# Sheet2.net
KiCad netlist of a schematic drawn in Altium Designer
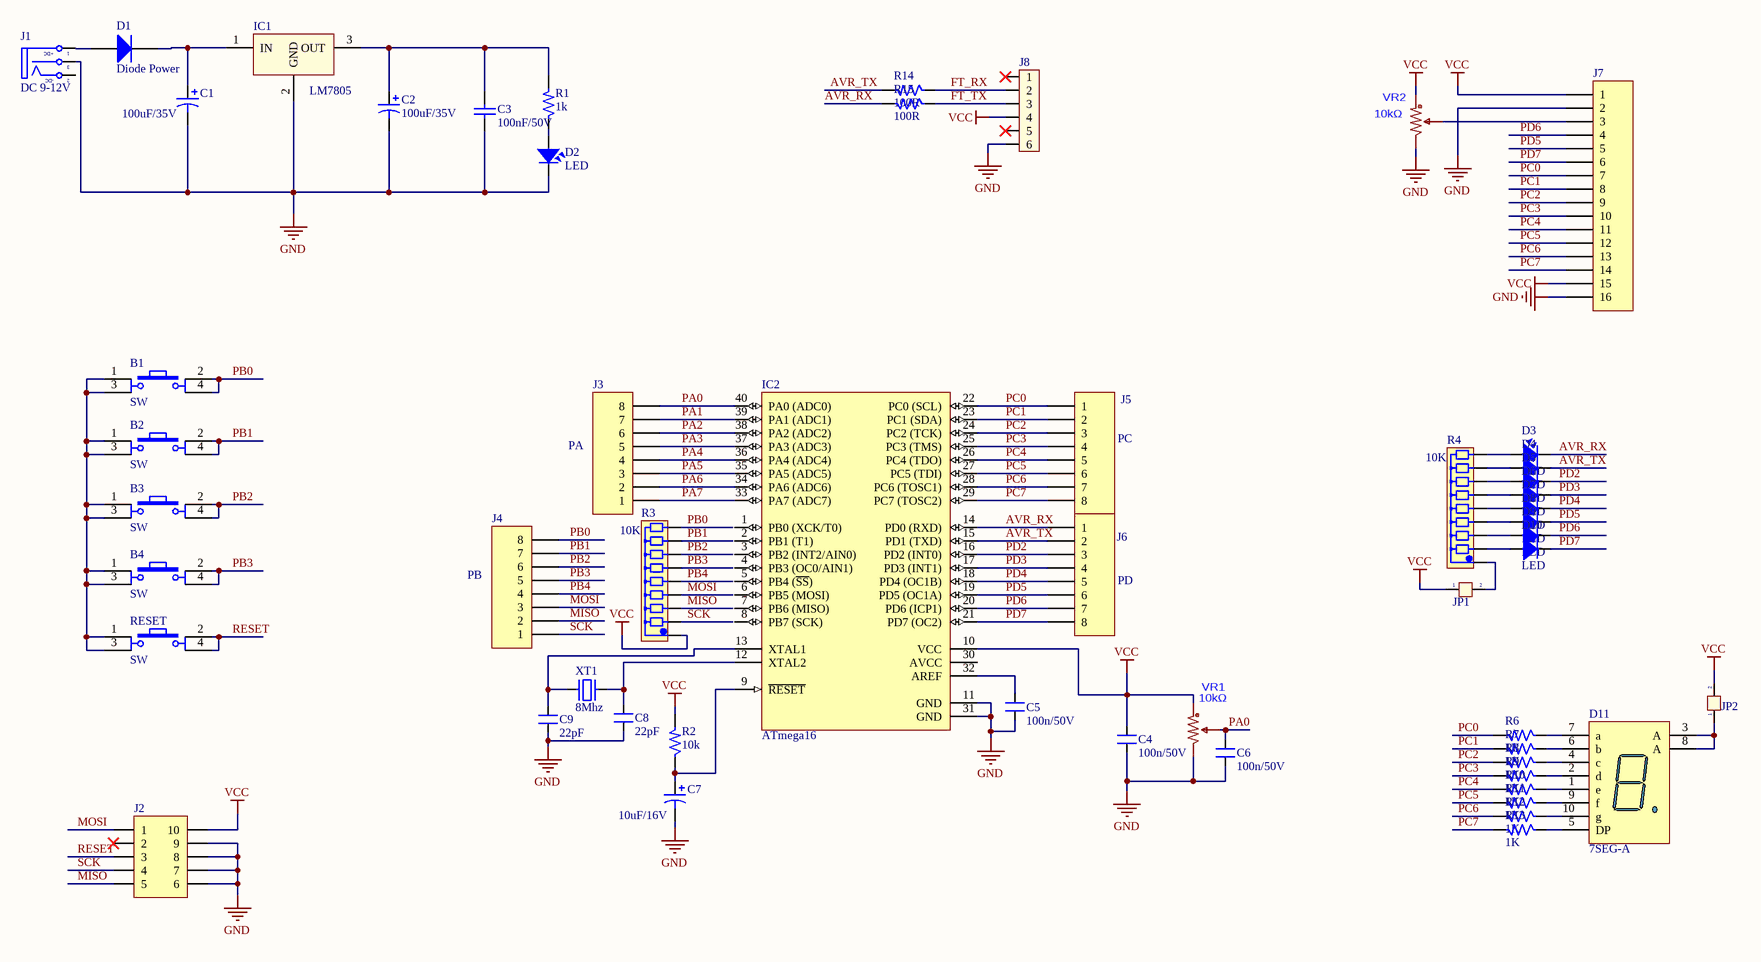
[diagram p0: Sheet2.SchDoc]

(export (version "E")
  (design (tool "Eeschema 10.0.6"))
  (components
    (comp (ref "B1")
      (value "SW")
      (footprint "SW4")
      (description "Switch button 4 pin")
      (libsource (lib "My Library") (part "SW4"))
    )
    (comp (ref "B2")
      (value "SW")
      (footprint "SW4")
      (description "Switch button 4 pin")
      (libsource (lib "My Library") (part "SW4"))
    )
    (comp (ref "B3")
      (value "SW")
      (footprint "SW4")
      (description "Switch button 4 pin")
      (libsource (lib "My Library") (part "SW4"))
    )
    (comp (ref "B4")
      (value "SW")
      (footprint "SW4")
      (description "Switch button 4 pin")
      (libsource (lib "My Library") (part "SW4"))
    )
    (comp (ref "C1")
      (value "100uF/35V")
      (footprint "C10mm")
      (description "Polarized Capacitor (Axial)")
      (fields (field (name "PUBLISHER") "Altium Limited"))
      (libsource (lib "My Library") (part "Cap Pol 8mm"))
    )
    (comp (ref "C2")
      (value "100uF/35V")
      (footprint "C10mm")
      (description "Polarized Capacitor (Axial)")
      (fields (field (name "PUBLISHER") "Altium Limited"))
      (libsource (lib "My Library") (part "Cap Pol 8mm"))
    )
    (comp (ref "C3")
      (value "100nF/50V")
      (footprint "Tu-pico")
      (description "Capacitor")
      (fields (field (name "Comment") "Capacitor Ceramic") (field (name "PUBLISHER") "Altium Limited"))
      (libsource (lib "My Library") (part "CapCeramic"))
    )
    (comp (ref "C4")
      (value "100n/50V")
      (footprint "CN1")
      (description "Cap np  1pF - 472pF")
      (libsource (lib "My Library") (part "CN1"))
    )
    (comp (ref "C5")
      (value "100n/50V")
      (footprint "CN1")
      (description "Cap np  1pF - 472pF")
      (libsource (lib "My Library") (part "CN1"))
    )
    (comp (ref "C6")
      (value "100n/50V")
      (footprint "CN1")
      (description "Cap np  1pF - 472pF")
      (libsource (lib "My Library") (part "CN1"))
    )
    (comp (ref "C7")
      (value "10uF/16V")
      (footprint "C5mm")
      (description "Polarized Capacitor (Axial)")
      (fields (field (name "PUBLISHER") "Altium Limited"))
      (libsource (lib "My Library") (part "Cap Pol 5mm"))
    )
    (comp (ref "C8")
      (value "22pF")
      (footprint "CN1")
      (description "Cap np  1pF - 472pF")
      (libsource (lib "My Library") (part "CN1"))
    )
    (comp (ref "C9")
      (value "22pF")
      (footprint "CN1")
      (description "Cap np  1pF - 472pF")
      (libsource (lib "My Library") (part "CN1"))
    )
    (comp (ref "D1")
      (value "Diode Power")
      (footprint "DIODE/POW/1A")
      (fields (field (name "PUBLISHER") "Altium Limited"))
      (libsource (lib "My Library") (part "Diode Power"))
    )
    (comp (ref "D2")
      (value "LED")
      (footprint "LED-5TRED")
      (description "LED Single colour Green and Red")
      (libsource (lib "My Library") (part "LED"))
    )
    (comp (ref "D3")
      (value "LED")
      (footprint "LED-5TRED")
      (description "LED Single colour Green and Red")
      (libsource (lib "My Library") (part "LED"))
    )
    (comp (ref "D4")
      (value "LED")
      (footprint "LED-5TRED")
      (description "LED Single colour Green and Red")
      (libsource (lib "My Library") (part "LED"))
    )
    (comp (ref "D5")
      (value "LED")
      (footprint "LED-5TRED")
      (description "LED Single colour Green and Red")
      (libsource (lib "My Library") (part "LED"))
    )
    (comp (ref "D6")
      (value "LED")
      (footprint "LED-5TRED")
      (description "LED Single colour Green and Red")
      (libsource (lib "My Library") (part "LED"))
    )
    (comp (ref "D7")
      (value "LED")
      (footprint "LED-5TRED")
      (description "LED Single colour Green and Red")
      (libsource (lib "My Library") (part "LED"))
    )
    (comp (ref "D8")
      (value "LED")
      (footprint "LED-5TRED")
      (description "LED Single colour Green and Red")
      (libsource (lib "My Library") (part "LED"))
    )
    (comp (ref "D9")
      (value "LED")
      (footprint "LED-5TRED")
      (description "LED Single colour Green and Red")
      (libsource (lib "My Library") (part "LED"))
    )
    (comp (ref "D10")
      (value "LED")
      (footprint "LED-5TRED")
      (description "LED Single colour Green and Red")
      (libsource (lib "My Library") (part "LED"))
    )
    (comp (ref "D11")
      (value "7SEG-A")
      (footprint "LED7SEG")
      (description "14.2 mm General Purpose Blue 7-Segment Display: CA, RH DP, Gray Surface")
      (fields (field (name "PUBLISHER") "Altium Limited"))
      (libsource (lib "My Library") (part "LED7SEG-A"))
    )
    (comp (ref "IC1")
      (value "LM7805")
      (footprint "QTO-220")
      (description "On ap +, from + 5 to + 24VDC")
      (libsource (lib "My Library") (part "LM78xx"))
    )
    (comp (ref "IC2")
      (value "ATmega16")
      (footprint "DIP40/W0.6")
      (description "8-Bit AVR Microcontroller with 16K Bytes of In-System Programmable Flash Memory")
      (libsource (lib "My Library") (part "ATmega16A-PU"))
    )
    (comp (ref "J1")
      (value "DC 9-12V")
      (footprint "DC-IN")
      (description "Jac DC input")
      (libsource (lib "My Library") (part "DCIN"))
    )
    (comp (ref "J2")
      (value "JP5x2")
      (footprint "JP5-D2T")
      (description "WR-PHD 2.54 mm Dual Socket Header")
      (fields
        (field (name "MANUFACTURER") "Würth Elektronik eiSos GmbH")
        (field (name "PARTNO") "61301021821")
        (field (name "CREATED BY") "Karrer Zheng")
      )
      (libsource (lib "My Library") (part "JP5x2"))
    )
    (comp (ref "J3")
      (value "PA")
      (footprint "HDR1X8")
      (description "Header, 8-Pin")
      (fields (field (name "PUBLISHER") "Altium Limited"))
      (libsource (lib "") (part "Header 8_1"))
    )
    (comp (ref "J4")
      (value "PB")
      (footprint "HDR1X8")
      (description "Header, 8-Pin")
      (fields (field (name "PUBLISHER") "Altium Limited"))
      (libsource (lib "") (part "Header 8_1"))
    )
    (comp (ref "J5")
      (value "PC")
      (footprint "HDR1X8")
      (description "Header, 8-Pin")
      (fields (field (name "PUBLISHER") "Altium Limited"))
      (libsource (lib "My Library") (part "Header 8"))
    )
    (comp (ref "J6")
      (value "PD")
      (footprint "HDR1X8")
      (description "Header, 8-Pin")
      (fields (field (name "PUBLISHER") "Altium Limited"))
      (libsource (lib "My Library") (part "Header 8"))
    )
    (comp (ref "J7")
      (value "JP16")
      (footprint "JP16-D1T")
      (description "WR-PHD 2.54 mm Angled Socket Header")
      (fields
        (field (name "MANUFACTURER") "Würth Elektronik eiSos GmbH")
        (field (name "PARTNO") "613016143121")
        (field (name "CREATED BY") "Karrer Zheng")
      )
      (libsource (lib "My Library") (part "JP16"))
    )
    (comp (ref "J8") (value "JP6 PIN") (footprint "JP6") (libsource (lib "My Library") (part "JP6")))
    (comp (ref "JP1") (value "Jumper 2") (footprint "JP2") (libsource (lib "") (part "JP 2_1")))
    (comp (ref "JP2") (value "Jumper 2") (footprint "JP2") (libsource (lib "My Library") (part "JP 2")))
    (comp (ref "R1")
      (value "1k")
      (footprint "R1/4W")
      (description "Resistor 1/4W")
      (libsource (lib "My Library") (part "R"))
    )
    (comp (ref "R2")
      (value "10k")
      (footprint "R1/4W")
      (description "Resistor 1/4W")
      (libsource (lib "My Library") (part "R"))
    )
    (comp (ref "R3")
      (value "10K")
      (footprint "RN8")
      (description "Resistor 8 (Thanh)")
      (libsource (lib "My Library") (part "RN8"))
    )
    (comp (ref "R4")
      (value "10K")
      (footprint "RN8")
      (description "Resistor 8 (Thanh)")
      (libsource (lib "My Library") (part "RN8"))
    )
    (comp (ref "R6")
      (value "1K")
      (footprint "R1/4W")
      (description "Resistor 1/4W")
      (libsource (lib "My Library") (part "R"))
    )
    (comp (ref "R7")
      (value "1K")
      (footprint "R1/4W")
      (description "Resistor 1/4W")
      (libsource (lib "My Library") (part "R"))
    )
    (comp (ref "R8")
      (value "1K")
      (footprint "R1/4W")
      (description "Resistor 1/4W")
      (libsource (lib "My Library") (part "R"))
    )
    (comp (ref "R9")
      (value "1K")
      (footprint "R1/4W")
      (description "Resistor 1/4W")
      (libsource (lib "My Library") (part "R"))
    )
    (comp (ref "R10")
      (value "1K")
      (footprint "R1/4W")
      (description "Resistor 1/4W")
      (libsource (lib "My Library") (part "R"))
    )
    (comp (ref "R11")
      (value "1K")
      (footprint "R1/4W")
      (description "Resistor 1/4W")
      (libsource (lib "My Library") (part "R"))
    )
    (comp (ref "R12")
      (value "1K")
      (footprint "R1/4W")
      (description "Resistor 1/4W")
      (libsource (lib "My Library") (part "R"))
    )
    (comp (ref "R13")
      (value "1K")
      (footprint "R1/4W")
      (description "Resistor 1/4W")
      (libsource (lib "My Library") (part "R"))
    )
    (comp (ref "R14")
      (value "100R")
      (footprint "R1/4W")
      (description "Resistor 1/4W")
      (libsource (lib "My Library") (part "R"))
    )
    (comp (ref "R15")
      (value "100R")
      (footprint "R1/4W")
      (description "Resistor 1/4W")
      (libsource (lib "My Library") (part "R"))
    )
    (comp (ref "RESET")
      (value "SW")
      (footprint "SW4")
      (description "Switch button 4 pin")
      (libsource (lib "My Library") (part "SW4"))
    )
    (comp (ref "VR1")
      (value "10kΩ")
      (footprint "RES-ADJ-SMD_RM065-V1")
      (description "VR-10K")
      (libsource (lib "My_Library_DPD_V2") (part "VR-RM065-103(10K)"))
    )
    (comp (ref "VR2")
      (value "10kΩ")
      (footprint "RES-ADJ-SMD_RM065-V1")
      (description "VR-10K")
      (libsource (lib "My_Library_DPD_V2") (part "VR-RM065-103(10K)"))
    )
    (comp (ref "XT1")
      (value "8Mhz")
      (footprint "XT2")
      (description "Crystal For all Crystal 2pin.")
      (libsource (lib "My Library") (part "XT2"))
    )
  )
  (nets
    (net (code "1") (name "/AVR_RX") (class "Default")
      (node (ref "D3") (pin "2") (pinfunction "2_2") (pintype "passive"))
      (node (ref "IC2") (pin "14") (pinfunction "PD0_(RXD)_14") (pintype "bidirectional"))
      (node (ref "J6") (pin "1") (pinfunction "1_1") (pintype "passive"))
      (node (ref "R15") (pin "2") (pinfunction "2_2") (pintype "passive"))
    )
    (net (code "2") (name "/AVR_TX") (class "Default")
      (node (ref "D4") (pin "2") (pinfunction "2_2") (pintype "passive"))
      (node (ref "IC2") (pin "15") (pinfunction "PD1_(TXD)_15") (pintype "bidirectional"))
      (node (ref "J6") (pin "2") (pinfunction "2_2") (pintype "passive"))
      (node (ref "R14") (pin "2") (pinfunction "2_2") (pintype "passive"))
    )
    (net (code "3") (name "/FT_RX") (class "Default")
      (node (ref "J8") (pin "2") (pinfunction "2_2") (pintype "passive"))
      (node (ref "R14") (pin "1") (pinfunction "1_1") (pintype "passive"))
    )
    (net (code "4") (name "/FT_TX") (class "Default")
      (node (ref "J8") (pin "3") (pinfunction "3_3") (pintype "passive"))
      (node (ref "R15") (pin "1") (pinfunction "1_1") (pintype "passive"))
    )
    (net (code "5") (name "/MISO") (class "Default")
      (node (ref "J2") (pin "5") (pinfunction "5_5") (pintype "passive"))
      (node (ref "J4") (pin "2") (pinfunction "2_2") (pintype "passive"))
      (node (ref "R3") (pin "3") (pinfunction "3_3") (pintype "passive"))
    )
    (net (code "6") (name "/MOSI") (class "Default")
      (node (ref "J2") (pin "1") (pinfunction "1_1") (pintype "passive"))
      (node (ref "J4") (pin "3") (pinfunction "3_3") (pintype "passive"))
      (node (ref "R3") (pin "4") (pinfunction "4_4") (pintype "passive"))
    )
    (net (code "7") (name "/PA0") (class "Default")
      (node (ref "C6") (pin "1") (pinfunction "1_1") (pintype "passive"))
      (node (ref "IC2") (pin "40") (pinfunction "PA0_(ADC0)_40") (pintype "bidirectional"))
      (node (ref "J3") (pin "8") (pinfunction "8_8") (pintype "passive"))
      (node (ref "VR1") (pin "2") (pinfunction "2_2") (pintype "passive"))
    )
    (net (code "8") (name "/PA1") (class "Default")
      (node (ref "IC2") (pin "39") (pinfunction "PA1_(ADC1)_39") (pintype "bidirectional"))
      (node (ref "J3") (pin "7") (pinfunction "7_7") (pintype "passive"))
    )
    (net (code "9") (name "/PA2") (class "Default")
      (node (ref "IC2") (pin "38") (pinfunction "PA2_(ADC2)_38") (pintype "bidirectional"))
      (node (ref "J3") (pin "6") (pinfunction "6_6") (pintype "passive"))
    )
    (net (code "10") (name "/PA3") (class "Default")
      (node (ref "IC2") (pin "37") (pinfunction "PA3_(ADC3)_37") (pintype "bidirectional"))
      (node (ref "J3") (pin "5") (pinfunction "5_5") (pintype "passive"))
    )
    (net (code "11") (name "/PA4") (class "Default")
      (node (ref "IC2") (pin "36") (pinfunction "PA4_(ADC4)_36") (pintype "bidirectional"))
      (node (ref "J3") (pin "4") (pinfunction "4_4") (pintype "passive"))
    )
    (net (code "12") (name "/PA5") (class "Default")
      (node (ref "IC2") (pin "35") (pinfunction "PA5_(ADC5)_35") (pintype "bidirectional"))
      (node (ref "J3") (pin "3") (pinfunction "3_3") (pintype "passive"))
    )
    (net (code "13") (name "/PA6") (class "Default")
      (node (ref "IC2") (pin "34") (pinfunction "PA6_(ADC6)_34") (pintype "bidirectional"))
      (node (ref "J3") (pin "2") (pinfunction "2_2") (pintype "passive"))
    )
    (net (code "14") (name "/PA7") (class "Default")
      (node (ref "IC2") (pin "33") (pinfunction "PA7_(ADC7)_33") (pintype "bidirectional"))
      (node (ref "J3") (pin "1") (pinfunction "1_1") (pintype "passive"))
    )
    (net (code "15") (name "/PB0") (class "Default")
      (node (ref "B1") (pin "2") (pintype "passive"))
      (node (ref "B1") (pin "4") (pintype "passive"))
      (node (ref "J4") (pin "8") (pinfunction "8_8") (pintype "passive"))
      (node (ref "R3") (pin "9") (pinfunction "9_9") (pintype "passive"))
    )
    (net (code "16") (name "/PB1") (class "Default")
      (node (ref "B2") (pin "2") (pintype "passive"))
      (node (ref "B2") (pin "4") (pintype "passive"))
      (node (ref "J4") (pin "7") (pinfunction "7_7") (pintype "passive"))
      (node (ref "R3") (pin "8") (pinfunction "8_8") (pintype "passive"))
    )
    (net (code "17") (name "/PB2") (class "Default")
      (node (ref "B3") (pin "2") (pintype "passive"))
      (node (ref "B3") (pin "4") (pintype "passive"))
      (node (ref "J4") (pin "6") (pinfunction "6_6") (pintype "passive"))
      (node (ref "R3") (pin "7") (pinfunction "7_7") (pintype "passive"))
    )
    (net (code "18") (name "/PB3") (class "Default")
      (node (ref "B4") (pin "2") (pintype "passive"))
      (node (ref "B4") (pin "4") (pintype "passive"))
      (node (ref "J4") (pin "5") (pinfunction "5_5") (pintype "passive"))
      (node (ref "R3") (pin "6") (pinfunction "6_6") (pintype "passive"))
    )
    (net (code "19") (name "/PB4") (class "Default")
      (node (ref "J4") (pin "4") (pinfunction "4_4") (pintype "passive"))
      (node (ref "R3") (pin "5") (pinfunction "5_5") (pintype "passive"))
    )
    (net (code "20") (name "/PC0") (class "Default")
      (node (ref "IC2") (pin "22") (pinfunction "PC0_(SCL)_22") (pintype "bidirectional"))
      (node (ref "J5") (pin "1") (pinfunction "1_1") (pintype "passive"))
      (node (ref "J7") (pin "7") (pinfunction "7_7") (pintype "passive"))
      (node (ref "R6") (pin "2") (pinfunction "2_2") (pintype "passive"))
    )
    (net (code "21") (name "/PC1") (class "Default")
      (node (ref "IC2") (pin "23") (pinfunction "PC1_(SDA)_23") (pintype "bidirectional"))
      (node (ref "J5") (pin "2") (pinfunction "2_2") (pintype "passive"))
      (node (ref "J7") (pin "8") (pinfunction "8_8") (pintype "passive"))
      (node (ref "R7") (pin "2") (pinfunction "2_2") (pintype "passive"))
    )
    (net (code "22") (name "/PC2") (class "Default")
      (node (ref "IC2") (pin "24") (pinfunction "PC2_(TCK)_24") (pintype "bidirectional"))
      (node (ref "J5") (pin "3") (pinfunction "3_3") (pintype "passive"))
      (node (ref "J7") (pin "9") (pinfunction "9_9") (pintype "passive"))
      (node (ref "R8") (pin "2") (pinfunction "2_2") (pintype "passive"))
    )
    (net (code "23") (name "/PC3") (class "Default")
      (node (ref "IC2") (pin "25") (pinfunction "PC3_(TMS)_25") (pintype "bidirectional"))
      (node (ref "J5") (pin "4") (pinfunction "4_4") (pintype "passive"))
      (node (ref "J7") (pin "10") (pinfunction "10_10") (pintype "passive"))
      (node (ref "R9") (pin "2") (pinfunction "2_2") (pintype "passive"))
    )
    (net (code "24") (name "/PC4") (class "Default")
      (node (ref "IC2") (pin "26") (pinfunction "PC4_(TDO)_26") (pintype "bidirectional"))
      (node (ref "J5") (pin "5") (pinfunction "5_5") (pintype "passive"))
      (node (ref "J7") (pin "11") (pinfunction "11_11") (pintype "passive"))
      (node (ref "R10") (pin "2") (pinfunction "2_2") (pintype "passive"))
    )
    (net (code "25") (name "/PC5") (class "Default")
      (node (ref "IC2") (pin "27") (pinfunction "PC5_(TDI)_27") (pintype "bidirectional"))
      (node (ref "J5") (pin "6") (pinfunction "6_6") (pintype "passive"))
      (node (ref "J7") (pin "12") (pinfunction "12_12") (pintype "passive"))
      (node (ref "R11") (pin "2") (pinfunction "2_2") (pintype "passive"))
    )
    (net (code "26") (name "/PC6") (class "Default")
      (node (ref "IC2") (pin "28") (pinfunction "PC6_(TOSC1)_28") (pintype "bidirectional"))
      (node (ref "J5") (pin "7") (pinfunction "7_7") (pintype "passive"))
      (node (ref "J7") (pin "13") (pinfunction "13_13") (pintype "passive"))
      (node (ref "R12") (pin "2") (pinfunction "2_2") (pintype "passive"))
    )
    (net (code "27") (name "/PC7") (class "Default")
      (node (ref "IC2") (pin "29") (pinfunction "PC7_(TOSC2)_29") (pintype "bidirectional"))
      (node (ref "J5") (pin "8") (pinfunction "8_8") (pintype "passive"))
      (node (ref "J7") (pin "14") (pinfunction "14_14") (pintype "passive"))
      (node (ref "R13") (pin "2") (pinfunction "2_2") (pintype "passive"))
    )
    (net (code "28") (name "/PD2") (class "Default")
      (node (ref "D5") (pin "2") (pinfunction "2_2") (pintype "passive"))
      (node (ref "IC2") (pin "16") (pinfunction "PD2_(INT0)_16") (pintype "bidirectional"))
      (node (ref "J6") (pin "3") (pinfunction "3_3") (pintype "passive"))
    )
    (net (code "29") (name "/PD3") (class "Default")
      (node (ref "D6") (pin "2") (pinfunction "2_2") (pintype "passive"))
      (node (ref "IC2") (pin "17") (pinfunction "PD3_(INT1)_17") (pintype "bidirectional"))
      (node (ref "J6") (pin "4") (pinfunction "4_4") (pintype "passive"))
    )
    (net (code "30") (name "/PD4") (class "Default")
      (node (ref "D7") (pin "2") (pinfunction "2_2") (pintype "passive"))
      (node (ref "IC2") (pin "18") (pinfunction "PD4_(OC1B)_18") (pintype "bidirectional"))
      (node (ref "J6") (pin "5") (pinfunction "5_5") (pintype "passive"))
    )
    (net (code "31") (name "/PD5") (class "Default")
      (node (ref "D8") (pin "2") (pinfunction "2_2") (pintype "passive"))
      (node (ref "IC2") (pin "19") (pinfunction "PD5_(OC1A)_19") (pintype "bidirectional"))
      (node (ref "J6") (pin "6") (pinfunction "6_6") (pintype "passive"))
      (node (ref "J7") (pin "5") (pinfunction "5_5") (pintype "passive"))
    )
    (net (code "32") (name "/PD6") (class "Default")
      (node (ref "D9") (pin "2") (pinfunction "2_2") (pintype "passive"))
      (node (ref "IC2") (pin "20") (pinfunction "PD6_(ICP1)_20") (pintype "bidirectional"))
      (node (ref "J6") (pin "7") (pinfunction "7_7") (pintype "passive"))
      (node (ref "J7") (pin "4") (pinfunction "4_4") (pintype "passive"))
    )
    (net (code "33") (name "/PD7") (class "Default")
      (node (ref "D10") (pin "2") (pinfunction "2_2") (pintype "passive"))
      (node (ref "IC2") (pin "21") (pinfunction "PD7_(OC2)_21") (pintype "bidirectional"))
      (node (ref "J6") (pin "8") (pinfunction "8_8") (pintype "passive"))
      (node (ref "J7") (pin "6") (pinfunction "6_6") (pintype "passive"))
    )
    (net (code "34") (name "/RESET") (class "Default")
      (node (ref "J2") (pin "3") (pinfunction "3_3") (pintype "passive"))
      (node (ref "RESET") (pin "2") (pintype "passive"))
      (node (ref "RESET") (pin "4") (pintype "passive"))
    )
    (net (code "35") (name "/SCK") (class "Default")
      (node (ref "J2") (pin "4") (pinfunction "4_4") (pintype "passive"))
      (node (ref "J4") (pin "1") (pinfunction "1_1") (pintype "passive"))
      (node (ref "R3") (pin "2") (pinfunction "2_2") (pintype "passive"))
    )
    (net (code "36") (name "GND") (class "Default")
      (node (ref "C1") (pin "2") (pinfunction "2_2") (pintype "passive"))
      (node (ref "C2") (pin "2") (pinfunction "2_2") (pintype "passive"))
      (node (ref "C3") (pin "1") (pinfunction "1_1") (pintype "passive"))
      (node (ref "C4") (pin "2") (pinfunction "2_2") (pintype "passive"))
      (node (ref "C5") (pin "2") (pinfunction "2_2") (pintype "passive"))
      (node (ref "C6") (pin "2") (pinfunction "2_2") (pintype "passive"))
      (node (ref "C7") (pin "2") (pinfunction "2_2") (pintype "passive"))
      (node (ref "C8") (pin "1") (pinfunction "1_1") (pintype "passive"))
      (node (ref "C9") (pin "1") (pinfunction "1_1") (pintype "passive"))
      (node (ref "D2") (pin "2") (pinfunction "2_2") (pintype "passive"))
      (node (ref "IC1") (pin "2") (pinfunction "GND_2") (pintype "passive"))
      (node (ref "IC2") (pin "11") (pinfunction "GND_11") (pintype "power_in"))
      (node (ref "IC2") (pin "31") (pinfunction "GND_31") (pintype "power_in"))
      (node (ref "J1") (pin "3") (pinfunction "S_3") (pintype "power_in"))
      (node (ref "J2") (pin "6") (pinfunction "6_6") (pintype "passive"))
      (node (ref "J2") (pin "7") (pinfunction "7_7") (pintype "passive"))
      (node (ref "J2") (pin "8") (pinfunction "8_8") (pintype "passive"))
      (node (ref "J2") (pin "9") (pinfunction "9_9") (pintype "passive"))
      (node (ref "J7") (pin "16") (pinfunction "16_16") (pintype "passive"))
      (node (ref "J7") (pin "2") (pinfunction "2_2") (pintype "passive"))
      (node (ref "J8") (pin "6") (pinfunction "6_6") (pintype "passive"))
      (node (ref "VR1") (pin "3") (pinfunction "3_3") (pintype "passive"))
      (node (ref "VR2") (pin "3") (pinfunction "3_3") (pintype "passive"))
    )
    (net (code "37") (name "Net-(B1-Pad1)") (class "Default")
      (node (ref "B1") (pin "1") (pintype "passive"))
      (node (ref "B1") (pin "3") (pintype "passive"))
      (node (ref "B2") (pin "1") (pintype "passive"))
      (node (ref "B2") (pin "3") (pintype "passive"))
      (node (ref "B3") (pin "1") (pintype "passive"))
      (node (ref "B3") (pin "3") (pintype "passive"))
      (node (ref "B4") (pin "1") (pintype "passive"))
      (node (ref "B4") (pin "3") (pintype "passive"))
      (node (ref "RESET") (pin "1") (pintype "passive"))
      (node (ref "RESET") (pin "3") (pintype "passive"))
    )
    (net (code "38") (name "Net-(D1-A)") (class "Default")
      (node (ref "D1") (pin "1") (pinfunction "A_1") (pintype "passive"))
      (node (ref "J1") (pin "1") (pinfunction "T_1") (pintype "passive"))
    )
    (net (code "39") (name "Net-(D1-K)") (class "Default")
      (node (ref "C1") (pin "1") (pinfunction "1_1") (pintype "passive"))
      (node (ref "D1") (pin "2") (pinfunction "K_2") (pintype "passive"))
      (node (ref "IC1") (pin "1") (pinfunction "IN_1") (pintype "passive"))
    )
    (net (code "40") (name "Net-(D2-Pad1)") (class "Default")
      (node (ref "D2") (pin "1") (pinfunction "1_1") (pintype "passive"))
      (node (ref "R1") (pin "1") (pinfunction "1_1") (pintype "passive"))
    )
    (net (code "41") (name "Net-(D3-Pad1)") (class "Default")
      (node (ref "D3") (pin "1") (pinfunction "1_1") (pintype "passive"))
      (node (ref "R4") (pin "9") (pinfunction "9_9") (pintype "passive"))
    )
    (net (code "42") (name "Net-(D4-Pad1)") (class "Default")
      (node (ref "D4") (pin "1") (pinfunction "1_1") (pintype "passive"))
      (node (ref "R4") (pin "8") (pinfunction "8_8") (pintype "passive"))
    )
    (net (code "43") (name "Net-(D5-Pad1)") (class "Default")
      (node (ref "D5") (pin "1") (pinfunction "1_1") (pintype "passive"))
      (node (ref "R4") (pin "7") (pinfunction "7_7") (pintype "passive"))
    )
    (net (code "44") (name "Net-(D6-Pad1)") (class "Default")
      (node (ref "D6") (pin "1") (pinfunction "1_1") (pintype "passive"))
      (node (ref "R4") (pin "6") (pinfunction "6_6") (pintype "passive"))
    )
    (net (code "45") (name "Net-(D7-Pad1)") (class "Default")
      (node (ref "D7") (pin "1") (pinfunction "1_1") (pintype "passive"))
      (node (ref "R4") (pin "5") (pinfunction "5_5") (pintype "passive"))
    )
    (net (code "46") (name "Net-(D8-Pad1)") (class "Default")
      (node (ref "D8") (pin "1") (pinfunction "1_1") (pintype "passive"))
      (node (ref "R4") (pin "4") (pinfunction "4_4") (pintype "passive"))
    )
    (net (code "47") (name "Net-(D9-Pad1)") (class "Default")
      (node (ref "D9") (pin "1") (pinfunction "1_1") (pintype "passive"))
      (node (ref "R4") (pin "3") (pinfunction "3_3") (pintype "passive"))
    )
    (net (code "48") (name "Net-(D10-Pad1)") (class "Default")
      (node (ref "D10") (pin "1") (pinfunction "1_1") (pintype "passive"))
      (node (ref "R4") (pin "2") (pinfunction "2_2") (pintype "passive"))
    )
    (net (code "49") (name "Net-(D11-A-Pad3)") (class "Default")
      (node (ref "D11") (pin "3") (pinfunction "A_3") (pintype "passive"))
      (node (ref "D11") (pin "8") (pinfunction "A_8") (pintype "passive"))
      (node (ref "JP2") (pin "1") (pinfunction "1_1") (pintype "passive"))
    )
    (net (code "50") (name "Net-(D11-DP)") (class "Default")
      (node (ref "D11") (pin "5") (pinfunction "DP_5") (pintype "passive"))
      (node (ref "R13") (pin "1") (pinfunction "1_1") (pintype "passive"))
    )
    (net (code "51") (name "Net-(D11-a)") (class "Default")
      (node (ref "D11") (pin "7") (pinfunction "a_7") (pintype "passive"))
      (node (ref "R6") (pin "1") (pinfunction "1_1") (pintype "passive"))
    )
    (net (code "52") (name "Net-(D11-b)") (class "Default")
      (node (ref "D11") (pin "6") (pinfunction "b_6") (pintype "passive"))
      (node (ref "R7") (pin "1") (pinfunction "1_1") (pintype "passive"))
    )
    (net (code "53") (name "Net-(D11-c)") (class "Default")
      (node (ref "D11") (pin "4") (pinfunction "c_4") (pintype "passive"))
      (node (ref "R8") (pin "1") (pinfunction "1_1") (pintype "passive"))
    )
    (net (code "54") (name "Net-(D11-d)") (class "Default")
      (node (ref "D11") (pin "2") (pinfunction "d_2") (pintype "passive"))
      (node (ref "R9") (pin "1") (pinfunction "1_1") (pintype "passive"))
    )
    (net (code "55") (name "Net-(D11-e)") (class "Default")
      (node (ref "D11") (pin "1") (pinfunction "e_1") (pintype "passive"))
      (node (ref "R10") (pin "1") (pinfunction "1_1") (pintype "passive"))
    )
    (net (code "56") (name "Net-(D11-f)") (class "Default")
      (node (ref "D11") (pin "9") (pinfunction "f_9") (pintype "passive"))
      (node (ref "R11") (pin "1") (pinfunction "1_1") (pintype "passive"))
    )
    (net (code "57") (name "Net-(D11-g)") (class "Default")
      (node (ref "D11") (pin "10") (pinfunction "g_10") (pintype "passive"))
      (node (ref "R12") (pin "1") (pinfunction "1_1") (pintype "passive"))
    )
    (net (code "58") (name "Net-(IC1-OUT)") (class "Default")
      (node (ref "C2") (pin "1") (pinfunction "1_1") (pintype "passive"))
      (node (ref "C3") (pin "2") (pinfunction "2_2") (pintype "passive"))
      (node (ref "IC1") (pin "3") (pinfunction "OUT_3") (pintype "passive"))
      (node (ref "R1") (pin "2") (pinfunction "2_2") (pintype "passive"))
    )
    (net (code "59") (name "Net-(IC2-AREF)") (class "Default")
      (node (ref "C5") (pin "1") (pinfunction "1_1") (pintype "passive"))
      (node (ref "IC2") (pin "32") (pinfunction "AREF_32") (pintype "power_in"))
    )
    (net (code "60") (name "Net-(IC2-XTAL1)") (class "Default")
      (node (ref "C9") (pin "2") (pinfunction "2_2") (pintype "passive"))
      (node (ref "IC2") (pin "13") (pinfunction "XTAL1_13") (pintype "passive"))
      (node (ref "XT1") (pin "1") (pinfunction "1_1") (pintype "passive"))
    )
    (net (code "61") (name "Net-(IC2-XTAL2)") (class "Default")
      (node (ref "C8") (pin "2") (pinfunction "2_2") (pintype "passive"))
      (node (ref "IC2") (pin "12") (pinfunction "XTAL2_12") (pintype "passive"))
      (node (ref "XT1") (pin "2") (pinfunction "2_2") (pintype "passive"))
    )
    (net (code "62") (name "Net-(IC2-~{RESET})") (class "Default")
      (node (ref "C7") (pin "1") (pinfunction "1_1") (pintype "passive"))
      (node (ref "IC2") (pin "9") (pinfunction "~{RESET}_9") (pintype "input"))
      (node (ref "R2") (pin "1") (pinfunction "1_1") (pintype "passive"))
    )
    (net (code "63") (name "Net-(J7-Pad3)") (class "Default")
      (node (ref "J7") (pin "3") (pinfunction "3_3") (pintype "passive"))
      (node (ref "VR2") (pin "2") (pinfunction "2_2") (pintype "passive"))
    )
    (net (code "64") (name "Net-(JP1-Pad2)") (class "Default")
      (node (ref "JP1") (pin "2") (pinfunction "2_2") (pintype "passive"))
      (node (ref "R4") (pin "1") (pinfunction "1_1") (pintype "passive"))
    )
    (net (code "65") (name "VCC") (class "Default")
      (node (ref "C4") (pin "1") (pinfunction "1_1") (pintype "passive"))
      (node (ref "IC2") (pin "10") (pinfunction "VCC_10") (pintype "power_in"))
      (node (ref "J2") (pin "10") (pinfunction "10_10") (pintype "passive"))
      (node (ref "J7") (pin "1") (pinfunction "1_1") (pintype "passive"))
      (node (ref "J7") (pin "15") (pinfunction "15_15") (pintype "passive"))
      (node (ref "J8") (pin "4") (pinfunction "4_4") (pintype "passive"))
      (node (ref "JP1") (pin "1") (pinfunction "1_1") (pintype "passive"))
      (node (ref "JP2") (pin "2") (pinfunction "2_2") (pintype "passive"))
      (node (ref "R2") (pin "2") (pinfunction "2_2") (pintype "passive"))
      (node (ref "R3") (pin "1") (pinfunction "1_1") (pintype "passive"))
      (node (ref "VR1") (pin "1") (pinfunction "1_1") (pintype "passive"))
      (node (ref "VR2") (pin "1") (pinfunction "1_1") (pintype "passive"))
    )
    (net (code "66") (name "unconnected-(IC2-AVCC-Pad30)") (class "Default")
      (node (ref "IC2") (pin "30") (pinfunction "AVCC_30") (pintype "power_in"))
    )
    (net (code "67") (name "unconnected-(IC2-PB0_(XCK{slash}T0)-Pad1)") (class "Default")
      (node (ref "IC2") (pin "1") (pinfunction "PB0_(XCK/T0)_1") (pintype "bidirectional"))
    )
    (net (code "68") (name "unconnected-(IC2-PB1_(T1)-Pad2)") (class "Default")
      (node (ref "IC2") (pin "2") (pinfunction "PB1_(T1)_2") (pintype "bidirectional"))
    )
    (net (code "69") (name "unconnected-(IC2-PB2_(INT2{slash}AIN0)-Pad3)") (class "Default")
      (node (ref "IC2") (pin "3") (pinfunction "PB2_(INT2/AIN0)_3") (pintype "bidirectional"))
    )
    (net (code "70") (name "unconnected-(IC2-PB3_(OC0{slash}AIN1)-Pad4)") (class "Default")
      (node (ref "IC2") (pin "4") (pinfunction "PB3_(OC0/AIN1)_4") (pintype "bidirectional"))
    )
    (net (code "71") (name "unconnected-(IC2-PB4_(~{SS})-Pad5)") (class "Default")
      (node (ref "IC2") (pin "5") (pinfunction "PB4_(~{SS})_5") (pintype "bidirectional"))
    )
    (net (code "72") (name "unconnected-(IC2-PB5_(MOSI)-Pad6)") (class "Default")
      (node (ref "IC2") (pin "6") (pinfunction "PB5_(MOSI)_6") (pintype "bidirectional"))
    )
    (net (code "73") (name "unconnected-(IC2-PB6_(MISO)-Pad7)") (class "Default")
      (node (ref "IC2") (pin "7") (pinfunction "PB6_(MISO)_7") (pintype "bidirectional"))
    )
    (net (code "74") (name "unconnected-(IC2-PB7_(SCK)-Pad8)") (class "Default")
      (node (ref "IC2") (pin "8") (pinfunction "PB7_(SCK)_8") (pintype "bidirectional"))
    )
    (net (code "75") (name "unconnected-(J1-TN-Pad2)") (class "Default")
      (node (ref "J1") (pin "2") (pinfunction "TN_2") (pintype "passive"))
    )
    (net (code "76") (name "unconnected-(J2-Pad2)") (class "Default")
      (node (ref "J2") (pin "2") (pinfunction "2_2") (pintype "passive+no_connect"))
    )
    (net (code "77") (name "unconnected-(J8-Pad1)") (class "Default")
      (node (ref "J8") (pin "1") (pinfunction "1_1") (pintype "passive+no_connect"))
    )
    (net (code "78") (name "unconnected-(J8-Pad5)") (class "Default")
      (node (ref "J8") (pin "5") (pinfunction "5_5") (pintype "passive+no_connect"))
    )
  )
)
